# UpTo11_FrontPanel.net
KiCad netlist of a schematic drawn in EAGLE
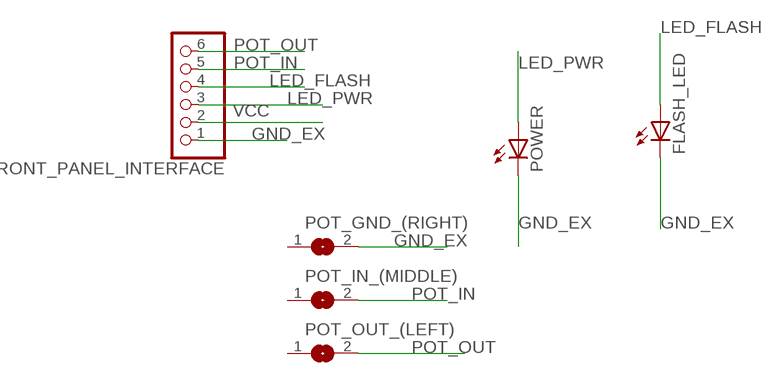
[diagram p0: schematic, sheet 1]

(export (version "E")
  (design (tool "Eeschema 10.0.6"))
  (components
    (comp (ref "FLASH_LED")
      (value "LED5MM")
      (footprint "eagle-import:LED5MM")
      (libsource (lib "eagle-import") (part "LED5MM"))
    )
    (comp (ref "FRONT_PANEL_INTERFACE")
      (value "PINHD-1X6")
      (footprint "eagle-import:1X06")
      (libsource (lib "eagle-import") (part "PINHD-1X6"))
    )
    (comp (ref "POT_GND_(RIGHT)")
      (value "SOLDERJUMPERREFLOW")
      (footprint "eagle-import:SOLDERJUMPER_REFLOW")
      (libsource (lib "eagle-import") (part "SOLDERJUMPERREFLOW"))
    )
    (comp (ref "POT_IN_(MIDDLE)")
      (value "SOLDERJUMPERREFLOW")
      (footprint "eagle-import:SOLDERJUMPER_REFLOW")
      (libsource (lib "eagle-import") (part "SOLDERJUMPERREFLOW"))
    )
    (comp (ref "POT_OUT_(LEFT)")
      (value "SOLDERJUMPERREFLOW")
      (footprint "eagle-import:SOLDERJUMPER_REFLOW")
      (libsource (lib "eagle-import") (part "SOLDERJUMPERREFLOW"))
    )
    (comp (ref "POWER")
      (value "LEDSMT1206")
      (footprint "eagle-import:1206")
      (libsource (lib "eagle-import") (part "LEDSMT1206"))
    )
  )
  (nets
    (net (code "1") (name "/GND_EX") (class "Default")
      (node (ref "FLASH_LED") (pin "K") (pinfunction "C_K") (pintype "passive"))
      (node (ref "FRONT_PANEL_INTERFACE") (pin "1") (pinfunction "1_1") (pintype "passive"))
      (node (ref "POT_GND_(RIGHT)") (pin "2") (pinfunction "2_2") (pintype "passive"))
      (node (ref "POWER") (pin "C") (pinfunction "C_C") (pintype "passive"))
    )
    (net (code "2") (name "/LED_FLASH") (class "Default")
      (node (ref "FLASH_LED") (pin "A") (pinfunction "A_A") (pintype "passive"))
      (node (ref "FRONT_PANEL_INTERFACE") (pin "4") (pinfunction "4_4") (pintype "passive"))
    )
    (net (code "3") (name "/LED_PWR") (class "Default")
      (node (ref "FRONT_PANEL_INTERFACE") (pin "3") (pinfunction "3_3") (pintype "passive"))
      (node (ref "POWER") (pin "A") (pinfunction "A_A") (pintype "passive"))
    )
    (net (code "4") (name "/POT_IN") (class "Default")
      (node (ref "FRONT_PANEL_INTERFACE") (pin "5") (pinfunction "5_5") (pintype "passive"))
      (node (ref "POT_IN_(MIDDLE)") (pin "2") (pinfunction "2_2") (pintype "passive"))
    )
    (net (code "5") (name "/POT_OUT") (class "Default")
      (node (ref "FRONT_PANEL_INTERFACE") (pin "6") (pinfunction "6_6") (pintype "passive"))
      (node (ref "POT_OUT_(LEFT)") (pin "2") (pinfunction "2_2") (pintype "passive"))
    )
    (net (code "6") (name "/VCC") (class "Default")
      (node (ref "FRONT_PANEL_INTERFACE") (pin "2") (pinfunction "2_2") (pintype "passive"))
    )
    (net (code "7") (name "unconnected-(POT_GND_(RIGHT)-Pad1)") (class "Default")
      (node (ref "POT_GND_(RIGHT)") (pin "1") (pinfunction "1_1") (pintype "passive"))
    )
    (net (code "8") (name "unconnected-(POT_IN_(MIDDLE)-Pad1)") (class "Default")
      (node (ref "POT_IN_(MIDDLE)") (pin "1") (pinfunction "1_1") (pintype "passive"))
    )
    (net (code "9") (name "unconnected-(POT_OUT_(LEFT)-Pad1)") (class "Default")
      (node (ref "POT_OUT_(LEFT)") (pin "1") (pinfunction "1_1") (pintype "passive"))
    )
  )
)
